# 3-CAN.net
KiCad netlist of a schematic drawn in Altium Designer
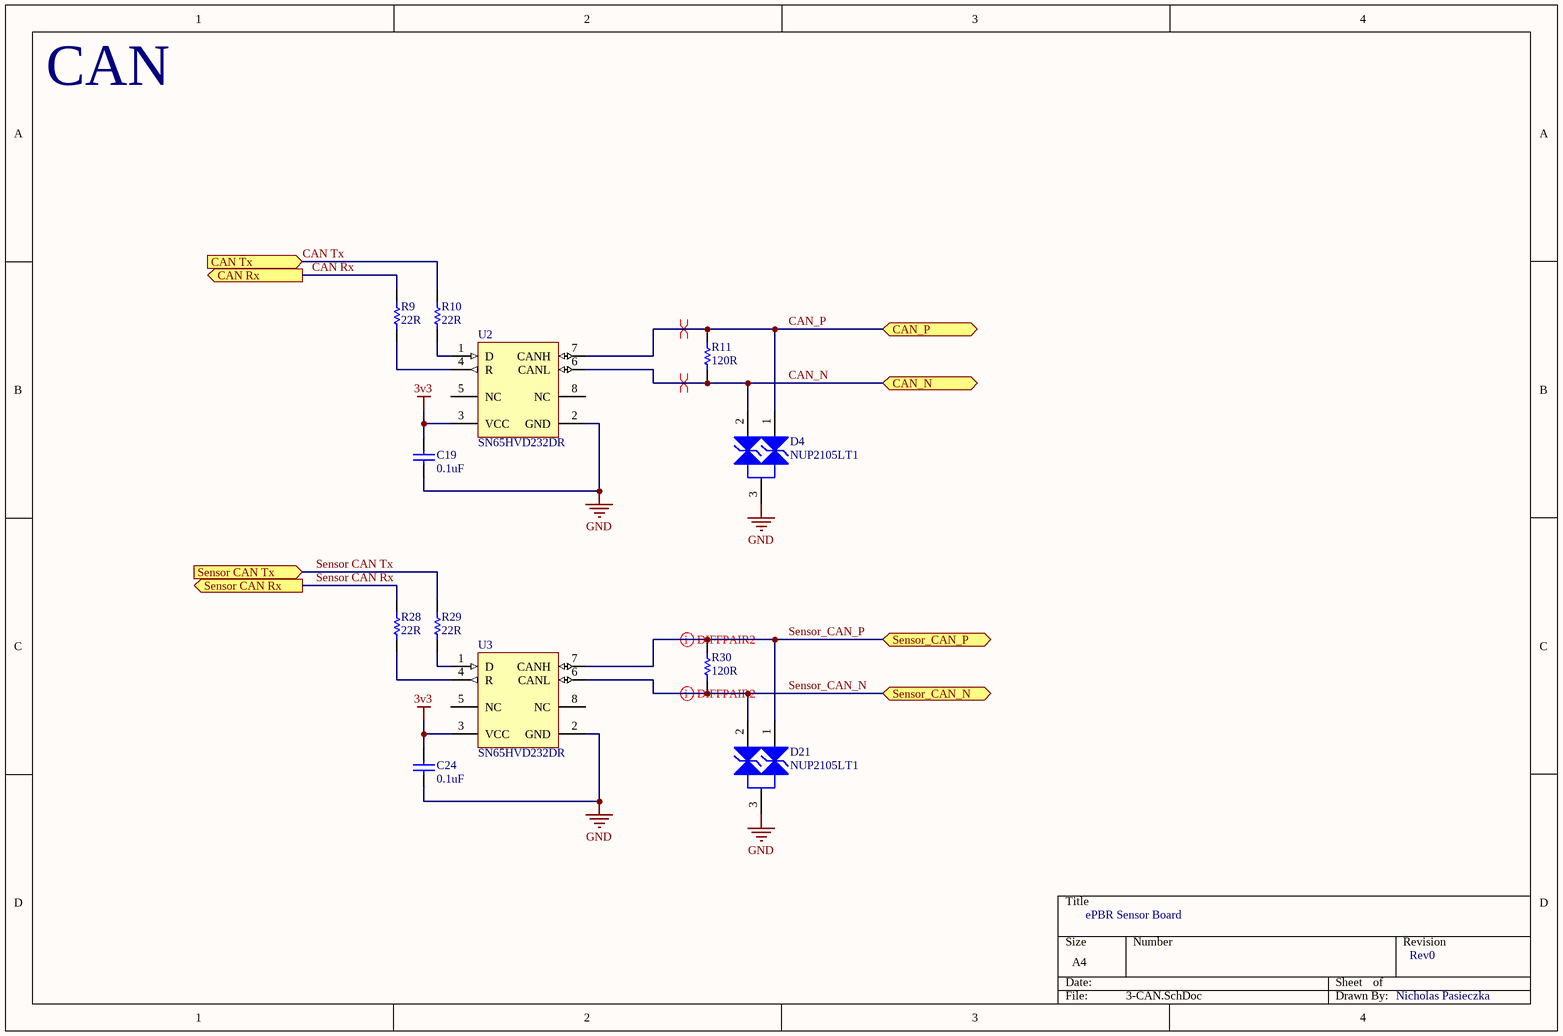
[diagram p0: 3-CAN.SchDoc]

(export (version "E")
  (design (tool "Eeschema 10.0.6"))
  (components
    (comp (ref "C19")
      (value "0.1uF")
      (footprint "CAPC1608X90X30NL10T20")
      (description "Chip Capacitor, 100 nF, +/- 10%, 50 V, -55 to 125 degC, 0603 (1608 Metric), RoHS, Tape and Reel")
      (fields (field (name "VOLTAGE") "50Vdc") (field (name "MANUFACTURER") "SamsungElectro-Mechanics"))
      (libsource (lib "Altium Content Vault") (part "CAP-NP-2"))
    )
    (comp (ref "C24")
      (value "0.1uF")
      (footprint "CAPC1608X90X30NL10T20")
      (description "Chip Capacitor, 100 nF, +/- 10%, 50 V, -55 to 125 degC, 0603 (1608 Metric), RoHS, Tape and Reel")
      (fields (field (name "VOLTAGE") "50Vdc") (field (name "MANUFACTURER") "SamsungElectro-Mechanics"))
      (libsource (lib "Altium Content Vault") (part "CAP-NP-2"))
    )
    (comp (ref "D4")
      (value "NUP2105LT1")
      (footprint "ONSC-SOT-23-3-318-08_V")
      (description "Dual Line CAN Bus Protector, 3-Pin SOT-23, Tape and Reel")
      (fields (field (name "MANUFACTURER") "On Semiconductor"))
      (libsource (lib "Altium Content Vault") (part "ONSC-NUP21X5X-SOT-23-3-318-08"))
    )
    (comp (ref "D21")
      (value "NUP2105LT1")
      (footprint "ONSC-SOT-23-3-318-08_V")
      (description "Dual Line CAN Bus Protector, 3-Pin SOT-23, Tape and Reel")
      (fields (field (name "MANUFACTURER") "On Semiconductor"))
      (libsource (lib "Altium Content Vault") (part "ONSC-NUP21X5X-SOT-23-3-318-08"))
    )
    (comp (ref "R9")
      (value "22R")
      (footprint "RESC0603(1608)_N")
      (description "22R 0.1W 5% 0603 (1608 Metric)  SMD")
      (fields (field (name "POWER") "0.1 W") (field (name "TOLERANCE") "5 %"))
      (libsource (lib "Altium Content Vault") (part "RES"))
    )
    (comp (ref "R10")
      (value "22R")
      (footprint "RESC0603(1608)_N")
      (description "22R 0.1W 5% 0603 (1608 Metric)  SMD")
      (fields (field (name "POWER") "0.1 W") (field (name "TOLERANCE") "5 %"))
      (libsource (lib "Altium Content Vault") (part "RES"))
    )
    (comp (ref "R11")
      (value "120R")
      (footprint "RESC0603(1608)_N")
      (description "120R 0.1W 5% 0603 (1608 Metric)  SMD")
      (fields (field (name "POWER") "0.1 W") (field (name "TOLERANCE") "5 %"))
      (libsource (lib "Altium Content Vault") (part "RES"))
    )
    (comp (ref "R28")
      (value "22R")
      (footprint "RESC0603(1608)_N")
      (description "22R 0.1W 5% 0603 (1608 Metric)  SMD")
      (fields (field (name "POWER") "0.1 W") (field (name "TOLERANCE") "5 %"))
      (libsource (lib "Altium Content Vault") (part "RES"))
    )
    (comp (ref "R29")
      (value "22R")
      (footprint "RESC0603(1608)_N")
      (description "22R 0.1W 5% 0603 (1608 Metric)  SMD")
      (fields (field (name "POWER") "0.1 W") (field (name "TOLERANCE") "5 %"))
      (libsource (lib "Altium Content Vault") (part "RES"))
    )
    (comp (ref "R30")
      (value "120R")
      (footprint "RESC0603(1608)_N")
      (description "120R 0.1W 5% 0603 (1608 Metric)  SMD")
      (fields (field (name "POWER") "0.1 W") (field (name "TOLERANCE") "5 %"))
      (libsource (lib "Altium Content Vault") (part "RES"))
    )
    (comp (ref "U2")
      (value "SN65HVD232DR")
      (footprint "D0008A_M")
      (description "3.3 V Can Transceiver, 17 mA, -40 to 85 degC, 8-pin SOIC (D), Green (RoHS & no Sb/Br)")
      (fields (field (name "MANUFACTURER") "Texas Instruments"))
      (libsource (lib "Altium Content Vault") (part "TI-SN65HVD232-SOIC_D-8"))
    )
    (comp (ref "U3")
      (value "SN65HVD232DR")
      (footprint "D0008A_M")
      (description "3.3 V Can Transceiver, 17 mA, -40 to 85 degC, 8-pin SOIC (D), Green (RoHS & no Sb/Br)")
      (fields (field (name "MANUFACTURER") "Texas Instruments"))
      (libsource (lib "Altium Content Vault") (part "TI-SN65HVD232-SOIC_D-8"))
    )
  )
  (nets
    (net (code "1") (name "/CAN Rx") (class "Default")
      (node (ref "R9") (pin "2") (pinfunction "2_2") (pintype "passive"))
    )
    (net (code "2") (name "/CAN Tx") (class "Default")
      (node (ref "R10") (pin "2") (pinfunction "2_2") (pintype "passive"))
    )
    (net (code "3") (name "/CAN_N") (class "Default")
      (node (ref "D4") (pin "2") (pinfunction "K_2") (pintype "passive"))
      (node (ref "R11") (pin "1") (pinfunction "1_1") (pintype "passive"))
      (node (ref "U2") (pin "6") (pinfunction "CANL_6") (pintype "bidirectional"))
    )
    (net (code "4") (name "/CAN_P") (class "Default")
      (node (ref "D4") (pin "1") (pinfunction "K_1") (pintype "passive"))
      (node (ref "R11") (pin "2") (pinfunction "2_2") (pintype "passive"))
      (node (ref "U2") (pin "7") (pinfunction "CANH_7") (pintype "bidirectional"))
    )
    (net (code "5") (name "/Sensor CAN Rx") (class "Default")
      (node (ref "R28") (pin "2") (pinfunction "2_2") (pintype "passive"))
    )
    (net (code "6") (name "/Sensor CAN Tx") (class "Default")
      (node (ref "R29") (pin "2") (pinfunction "2_2") (pintype "passive"))
    )
    (net (code "7") (name "/Sensor_CAN_N") (class "Default")
      (node (ref "D21") (pin "2") (pinfunction "K_2") (pintype "passive"))
      (node (ref "R30") (pin "1") (pinfunction "1_1") (pintype "passive"))
      (node (ref "U3") (pin "6") (pinfunction "CANL_6") (pintype "bidirectional"))
    )
    (net (code "8") (name "/Sensor_CAN_P") (class "Default")
      (node (ref "D21") (pin "1") (pinfunction "K_1") (pintype "passive"))
      (node (ref "R30") (pin "2") (pinfunction "2_2") (pintype "passive"))
      (node (ref "U3") (pin "7") (pinfunction "CANH_7") (pintype "bidirectional"))
    )
    (net (code "9") (name "3v3") (class "Default")
      (node (ref "C19") (pin "2") (pinfunction "2_2") (pintype "passive"))
      (node (ref "C24") (pin "2") (pinfunction "2_2") (pintype "passive"))
      (node (ref "U2") (pin "3") (pinfunction "VCC_3") (pintype "power_in"))
      (node (ref "U3") (pin "3") (pinfunction "VCC_3") (pintype "power_in"))
    )
    (net (code "10") (name "GND") (class "Default")
      (node (ref "C19") (pin "1") (pinfunction "1_1") (pintype "passive"))
      (node (ref "C24") (pin "1") (pinfunction "1_1") (pintype "passive"))
      (node (ref "D21") (pin "3") (pinfunction "K_3") (pintype "passive"))
      (node (ref "D4") (pin "3") (pinfunction "K_3") (pintype "passive"))
      (node (ref "U2") (pin "2") (pinfunction "GND_2") (pintype "power_in"))
      (node (ref "U3") (pin "2") (pinfunction "GND_2") (pintype "power_in"))
    )
    (net (code "11") (name "Net-(U2-D)") (class "Default")
      (node (ref "R10") (pin "1") (pinfunction "1_1") (pintype "passive"))
      (node (ref "U2") (pin "1") (pinfunction "D_1") (pintype "input"))
    )
    (net (code "12") (name "Net-(U2-R)") (class "Default")
      (node (ref "R9") (pin "1") (pinfunction "1_1") (pintype "passive"))
      (node (ref "U2") (pin "4") (pinfunction "R_4") (pintype "output"))
    )
    (net (code "13") (name "Net-(U3-D)") (class "Default")
      (node (ref "R29") (pin "1") (pinfunction "1_1") (pintype "passive"))
      (node (ref "U3") (pin "1") (pinfunction "D_1") (pintype "input"))
    )
    (net (code "14") (name "Net-(U3-R)") (class "Default")
      (node (ref "R28") (pin "1") (pinfunction "1_1") (pintype "passive"))
      (node (ref "U3") (pin "4") (pinfunction "R_4") (pintype "output"))
    )
    (net (code "15") (name "unconnected-(U2-NC-Pad5)") (class "Default")
      (node (ref "U2") (pin "5") (pinfunction "NC_5") (pintype "passive"))
    )
    (net (code "16") (name "unconnected-(U2-NC-Pad8)") (class "Default")
      (node (ref "U2") (pin "8") (pinfunction "NC_8") (pintype "passive"))
    )
    (net (code "17") (name "unconnected-(U3-NC-Pad5)") (class "Default")
      (node (ref "U3") (pin "5") (pinfunction "NC_5") (pintype "passive"))
    )
    (net (code "18") (name "unconnected-(U3-NC-Pad8)") (class "Default")
      (node (ref "U3") (pin "8") (pinfunction "NC_8") (pintype "passive"))
    )
  )
)
